# ESP_Batt_Board.net
KiCad netlist of a schematic drawn in Altium Designer
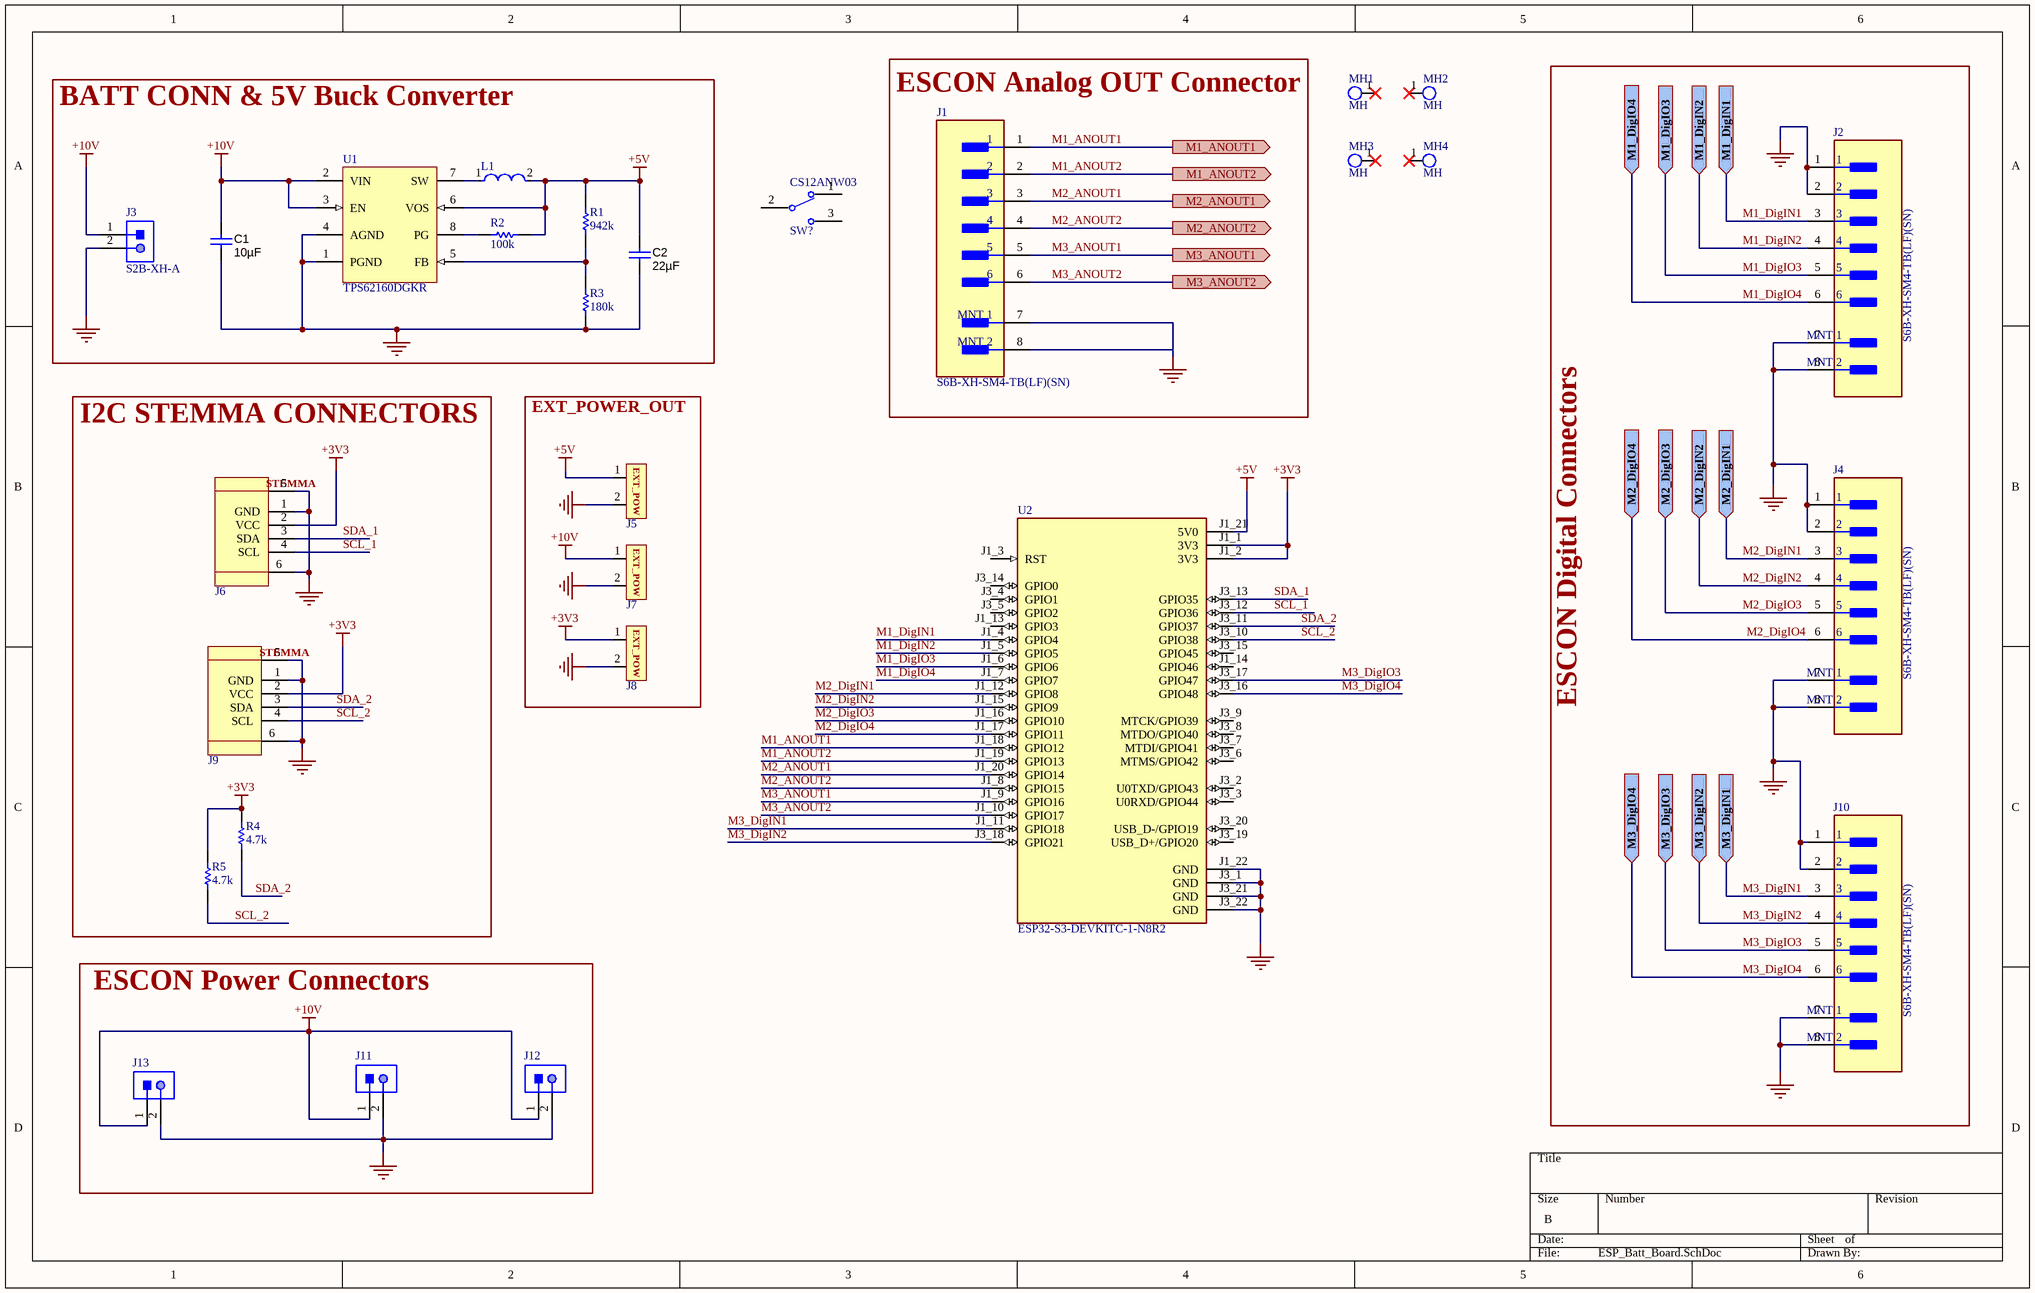
[diagram p0: ESP_Batt_Board.SchDoc]

(export (version "E")
  (design (tool "Eeschema 10.0.6"))
  (components
    (comp (ref "C1")
      (value "C2012X5R1E106K125AB")
      (footprint "CAP_0805")
      (description "CAP, CERM, 10uF, 25V, +/-10%, X5R, 0805")
      (fields
        (field (name "MANUFACTURER") "TDK")
        (field (name "VALUEDISPLAYED") "10µF")
        (field (name "PUBLISHER") "Texas Instruments")
      )
      (libsource (lib "Schematic") (part "C2012X5R1E106K125AB"))
    )
    (comp (ref "C2")
      (value "GRM21BR61E226ME44")
      (footprint "CAP_0805")
      (description "CAP, CERM, 22 µF, 25 V, +/- 20%, X5R, 0805")
      (fields (field (name "MANUFACTURER") "MuRata") (field (name "VALUEDISPLAYED") "22µF"))
      (libsource (lib "Schematic") (part "GRM21BR61E226ME44"))
    )
    (comp (ref "CS12ANW03")
      (value "SW?")
      (footprint "SPDT_SW")
      (libsource (lib "SchematicLib") (part "CS12ANW03"))
    )
    (comp (ref "J1")
      (value "S6B-XH-SM4-TB(LF)(SN)")
      (footprint "S6B-XH-SM4-TB")
      (description "CONN HEADER SMD R/A 6POS 2.5MM")
      (libsource (lib "") (part "S6B-XH-SM4-TB_1"))
    )
    (comp (ref "J2")
      (value "S6B-XH-SM4-TB(LF)(SN)")
      (footprint "S6B-XH-SM4-TB")
      (description "CONN HEADER SMD R/A 6POS 2.5MM")
      (libsource (lib "SchematicLib") (part "S6B-XH-SM4-TB"))
    )
    (comp (ref "J3")
      (value "S2B-XH-A")
      (footprint "JST-S2B-XH-A(LF)(SN)_V")
      (libsource (lib "SchematicLib") (part "S2B-XH-A"))
    )
    (comp (ref "J4")
      (value "S6B-XH-SM4-TB(LF)(SN)")
      (footprint "S6B-XH-SM4-TB")
      (description "CONN HEADER SMD R/A 6POS 2.5MM")
      (libsource (lib "SchematicLib") (part "S6B-XH-SM4-TB"))
    )
    (comp (ref "J5")
      (value "EXT_POWER_CONN")
      (footprint "EXTRA_POWR_CONN")
      (libsource (lib "SchematicLib") (part "EXT_POWER_CONN"))
    )
    (comp (ref "J6")
      (value "SM04B-SRSS-TB")
      (footprint "4PIN_STEMMA")
      (libsource (lib "SchematicLib") (part "SM04B-SRSS-TB"))
    )
    (comp (ref "J7")
      (value "EXT_POWER_CONN")
      (footprint "EXTRA_POWR_CONN")
      (libsource (lib "SchematicLib") (part "EXT_POWER_CONN"))
    )
    (comp (ref "J8")
      (value "EXT_POWER_CONN")
      (footprint "EXTRA_POWR_CONN")
      (libsource (lib "SchematicLib") (part "EXT_POWER_CONN"))
    )
    (comp (ref "J9")
      (value "SM04B-SRSS-TB")
      (footprint "4PIN_STEMMA")
      (libsource (lib "SchematicLib") (part "SM04B-SRSS-TB"))
    )
    (comp (ref "J10")
      (value "S6B-XH-SM4-TB(LF)(SN)")
      (footprint "S6B-XH-SM4-TB")
      (description "CONN HEADER SMD R/A 6POS 2.5MM")
      (libsource (lib "SchematicLib") (part "S6B-XH-SM4-TB"))
    )
    (comp (ref "J11")
      (value "S2B-XH-A")
      (footprint "JST-S2B-XH-A(LF)(SN)_V")
      (libsource (lib "") (part "S2B-XH-A_1"))
    )
    (comp (ref "J12")
      (value "S2B-XH-A")
      (footprint "JST-S2B-XH-A(LF)(SN)_V")
      (libsource (lib "") (part "S2B-XH-A_1"))
    )
    (comp (ref "J13")
      (value "S2B-XH-A")
      (footprint "JST-S2B-XH-A(LF)(SN)_V")
      (libsource (lib "") (part "S2B-XH-A_1"))
    )
    (comp (ref "L1")
      (value "IHLP1212BZEZ2R2M1Z")
      (footprint "IND_1212")
      (libsource (lib "SchematicLib") (part "IHLP1212BZEZ2R2M1Z"))
    )
    (comp (ref "MH1") (value "MH") (footprint "M3_MTH") (libsource (lib "SchematicLib") (part "M3_MTH")))
    (comp (ref "MH2") (value "MH") (footprint "M3_MTH") (libsource (lib "SchematicLib") (part "M3_MTH")))
    (comp (ref "MH3") (value "MH") (footprint "M3_MTH") (libsource (lib "SchematicLib") (part "M3_MTH")))
    (comp (ref "MH4") (value "MH") (footprint "M3_MTH") (libsource (lib "SchematicLib") (part "M3_MTH")))
    (comp (ref "R1") (value "942k") (footprint "RES_0603") (libsource (lib "SchematicLib") (part "RES_0603")))
    (comp (ref "R2") (value "100k") (footprint "RES_0603") (libsource (lib "SchematicLib") (part "RES_0603")))
    (comp (ref "R3") (value "180k") (footprint "RES_0603") (libsource (lib "SchematicLib") (part "RES_0603")))
    (comp (ref "R4") (value "4.7k") (footprint "RES_0603") (libsource (lib "SchematicLib") (part "RES_0603")))
    (comp (ref "R5") (value "4.7k") (footprint "RES_0603") (libsource (lib "SchematicLib") (part "RES_0603")))
    (comp (ref "U1")
      (value "TPS62160DGKR")
      (footprint "DGK0008A_M")
      (fields (field (name "MANUFACTURER") "Texas Instruments"))
      (libsource (lib "SchematicLib") (part "TPS62160DGKR"))
    )
    (comp (ref "U2")
      (value "ESP32-S3-DEVKITC-1-N8R2")
      (footprint "XCVR_ESP32-S3-DEVKITC-1-N8R2")
      (fields (field (name "MF") "Espressif Systems"))
      (libsource (lib "SchematicLib") (part "ESP32-S3-DEVKITC-1-N8R2"))
    )
  )
  (nets
    (net (code "1") (name "+3V3") (class "Default")
      (node (ref "J6") (pin "2") (pinfunction "VCC_2") (pintype "passive"))
      (node (ref "J8") (pin "1") (pinfunction "1_1") (pintype "passive"))
      (node (ref "J9") (pin "2") (pinfunction "VCC_2") (pintype "passive"))
      (node (ref "R4") (pin "2") (pinfunction "2_2") (pintype "passive"))
      (node (ref "R5") (pin "2") (pinfunction "2_2") (pintype "passive"))
      (node (ref "U2") (pin "J1_1") (pinfunction "3V3_J1_1") (pintype "power_in"))
      (node (ref "U2") (pin "J1_2") (pinfunction "3V3_J1_2") (pintype "power_in"))
    )
    (net (code "2") (name "+5V") (class "Default")
      (node (ref "C2") (pin "1") (pinfunction "1_1") (pintype "passive"))
      (node (ref "J5") (pin "1") (pinfunction "1_1") (pintype "passive"))
      (node (ref "L1") (pin "2") (pinfunction "2_2") (pintype "passive"))
      (node (ref "R1") (pin "2") (pinfunction "2_2") (pintype "passive"))
      (node (ref "R2") (pin "2") (pinfunction "2_2") (pintype "passive"))
      (node (ref "U1") (pin "6") (pinfunction "VOS_6") (pintype "input"))
      (node (ref "U2") (pin "J1_21") (pinfunction "5V0_J1_21") (pintype "power_in"))
    )
    (net (code "3") (name "+10V") (class "Default")
      (node (ref "C1") (pin "1") (pinfunction "1_1") (pintype "passive"))
      (node (ref "J11") (pin "1") (pinfunction "1_1") (pintype "passive"))
      (node (ref "J12") (pin "1") (pinfunction "1_1") (pintype "passive"))
      (node (ref "J13") (pin "1") (pinfunction "1_1") (pintype "passive"))
      (node (ref "J3") (pin "1") (pinfunction "1_1") (pintype "passive"))
      (node (ref "J7") (pin "1") (pinfunction "1_1") (pintype "passive"))
      (node (ref "U1") (pin "2") (pinfunction "VIN_2") (pintype "power_in"))
      (node (ref "U1") (pin "3") (pinfunction "EN_3") (pintype "input"))
    )
    (net (code "4") (name "/M1_ANOUT1") (class "Default")
      (node (ref "J1") (pin "1") (pinfunction "1_1") (pintype "passive"))
      (node (ref "U2") (pin "J1_18") (pinfunction "GPIO12_J1_18") (pintype "bidirectional"))
    )
    (net (code "5") (name "/M1_ANOUT2") (class "Default")
      (node (ref "J1") (pin "2") (pinfunction "2_2") (pintype "passive"))
      (node (ref "U2") (pin "J1_19") (pinfunction "GPIO13_J1_19") (pintype "bidirectional"))
    )
    (net (code "6") (name "/M1_DigIN1") (class "Default")
      (node (ref "J2") (pin "3") (pinfunction "3_3") (pintype "passive"))
      (node (ref "U2") (pin "J1_4") (pinfunction "GPIO4_J1_4") (pintype "bidirectional"))
    )
    (net (code "7") (name "/M1_DigIN2") (class "Default")
      (node (ref "J2") (pin "4") (pinfunction "4_4") (pintype "passive"))
      (node (ref "U2") (pin "J1_5") (pinfunction "GPIO5_J1_5") (pintype "bidirectional"))
    )
    (net (code "8") (name "/M1_DigIO3") (class "Default")
      (node (ref "J2") (pin "5") (pinfunction "5_5") (pintype "passive"))
      (node (ref "U2") (pin "J1_6") (pinfunction "GPIO6_J1_6") (pintype "bidirectional"))
    )
    (net (code "9") (name "/M1_DigIO4") (class "Default")
      (node (ref "J2") (pin "6") (pinfunction "6_6") (pintype "passive"))
      (node (ref "U2") (pin "J1_7") (pinfunction "GPIO7_J1_7") (pintype "bidirectional"))
    )
    (net (code "10") (name "/M2_ANOUT1") (class "Default")
      (node (ref "J1") (pin "3") (pinfunction "3_3") (pintype "passive"))
      (node (ref "U2") (pin "J1_20") (pinfunction "GPIO14_J1_20") (pintype "bidirectional"))
    )
    (net (code "11") (name "/M2_ANOUT2") (class "Default")
      (node (ref "J1") (pin "4") (pinfunction "4_4") (pintype "passive"))
      (node (ref "U2") (pin "J1_8") (pinfunction "GPIO15_J1_8") (pintype "bidirectional"))
    )
    (net (code "12") (name "/M2_DigIN1") (class "Default")
      (node (ref "J4") (pin "3") (pinfunction "3_3") (pintype "passive"))
      (node (ref "U2") (pin "J1_12") (pinfunction "GPIO8_J1_12") (pintype "bidirectional"))
    )
    (net (code "13") (name "/M2_DigIN2") (class "Default")
      (node (ref "J4") (pin "4") (pinfunction "4_4") (pintype "passive"))
      (node (ref "U2") (pin "J1_15") (pinfunction "GPIO9_J1_15") (pintype "bidirectional"))
    )
    (net (code "14") (name "/M2_DigIO3") (class "Default")
      (node (ref "J4") (pin "5") (pinfunction "5_5") (pintype "passive"))
      (node (ref "U2") (pin "J1_16") (pinfunction "GPIO10_J1_16") (pintype "bidirectional"))
    )
    (net (code "15") (name "/M2_DigIO4") (class "Default")
      (node (ref "J4") (pin "6") (pinfunction "6_6") (pintype "passive"))
      (node (ref "U2") (pin "J1_17") (pinfunction "GPIO11_J1_17") (pintype "bidirectional"))
    )
    (net (code "16") (name "/M3_ANOUT1") (class "Default")
      (node (ref "J1") (pin "5") (pinfunction "5_5") (pintype "passive"))
      (node (ref "U2") (pin "J1_9") (pinfunction "GPIO16_J1_9") (pintype "bidirectional"))
    )
    (net (code "17") (name "/M3_ANOUT2") (class "Default")
      (node (ref "J1") (pin "6") (pinfunction "6_6") (pintype "passive"))
      (node (ref "U2") (pin "J1_10") (pinfunction "GPIO17_J1_10") (pintype "bidirectional"))
    )
    (net (code "18") (name "/M3_DigIN1") (class "Default")
      (node (ref "J10") (pin "3") (pinfunction "3_3") (pintype "passive"))
      (node (ref "U2") (pin "J1_11") (pinfunction "GPIO18_J1_11") (pintype "bidirectional"))
    )
    (net (code "19") (name "/M3_DigIN2") (class "Default")
      (node (ref "J10") (pin "4") (pinfunction "4_4") (pintype "passive"))
      (node (ref "U2") (pin "J3_18") (pinfunction "GPIO21_J3_18") (pintype "bidirectional"))
    )
    (net (code "20") (name "/M3_DigIO3") (class "Default")
      (node (ref "J10") (pin "5") (pinfunction "5_5") (pintype "passive"))
      (node (ref "U2") (pin "J3_17") (pinfunction "GPIO47_J3_17") (pintype "bidirectional"))
    )
    (net (code "21") (name "/M3_DigIO4") (class "Default")
      (node (ref "J10") (pin "6") (pinfunction "6_6") (pintype "passive"))
      (node (ref "U2") (pin "J3_16") (pinfunction "GPIO48_J3_16") (pintype "bidirectional"))
    )
    (net (code "22") (name "/SCL_1") (class "Default")
      (node (ref "J6") (pin "4") (pinfunction "SCL_4") (pintype "passive"))
      (node (ref "U2") (pin "J3_12") (pinfunction "GPIO36_J3_12") (pintype "bidirectional"))
    )
    (net (code "23") (name "/SCL_2") (class "Default")
      (node (ref "J9") (pin "4") (pinfunction "SCL_4") (pintype "passive"))
      (node (ref "R5") (pin "1") (pinfunction "1_1") (pintype "passive"))
      (node (ref "U2") (pin "J3_10") (pinfunction "GPIO38_J3_10") (pintype "bidirectional"))
    )
    (net (code "24") (name "/SDA_1") (class "Default")
      (node (ref "J6") (pin "3") (pinfunction "SDA_3") (pintype "passive"))
      (node (ref "U2") (pin "J3_13") (pinfunction "GPIO35_J3_13") (pintype "bidirectional"))
    )
    (net (code "25") (name "/SDA_2") (class "Default")
      (node (ref "J9") (pin "3") (pinfunction "SDA_3") (pintype "passive"))
      (node (ref "R4") (pin "1") (pinfunction "1_1") (pintype "passive"))
      (node (ref "U2") (pin "J3_11") (pinfunction "GPIO37_J3_11") (pintype "bidirectional"))
    )
    (net (code "26") (name "GND") (class "Default")
      (node (ref "C1") (pin "2") (pinfunction "2_2") (pintype "passive"))
      (node (ref "C2") (pin "2") (pinfunction "2_2") (pintype "passive"))
      (node (ref "J1") (pin "7") (pinfunction "MNT_1_7") (pintype "passive"))
      (node (ref "J1") (pin "8") (pinfunction "MNT_2_8") (pintype "passive"))
      (node (ref "J10") (pin "1") (pinfunction "1_1") (pintype "passive"))
      (node (ref "J10") (pin "2") (pinfunction "2_2") (pintype "passive"))
      (node (ref "J10") (pin "7") (pinfunction "MNT_1_7") (pintype "passive"))
      (node (ref "J10") (pin "8") (pinfunction "MNT_2_8") (pintype "passive"))
      (node (ref "J11") (pin "2") (pinfunction "2_2") (pintype "passive"))
      (node (ref "J12") (pin "2") (pinfunction "2_2") (pintype "passive"))
      (node (ref "J13") (pin "2") (pinfunction "2_2") (pintype "passive"))
      (node (ref "J2") (pin "1") (pinfunction "1_1") (pintype "passive"))
      (node (ref "J2") (pin "2") (pinfunction "2_2") (pintype "passive"))
      (node (ref "J2") (pin "7") (pinfunction "MNT_1_7") (pintype "passive"))
      (node (ref "J2") (pin "8") (pinfunction "MNT_2_8") (pintype "passive"))
      (node (ref "J3") (pin "2") (pinfunction "2_2") (pintype "passive"))
      (node (ref "J4") (pin "1") (pinfunction "1_1") (pintype "passive"))
      (node (ref "J4") (pin "2") (pinfunction "2_2") (pintype "passive"))
      (node (ref "J4") (pin "7") (pinfunction "MNT_1_7") (pintype "passive"))
      (node (ref "J4") (pin "8") (pinfunction "MNT_2_8") (pintype "passive"))
      (node (ref "J5") (pin "2") (pinfunction "2_2") (pintype "passive"))
      (node (ref "J6") (pin "1") (pinfunction "GND_1") (pintype "passive"))
      (node (ref "J6") (pin "5") (pinfunction "MNT_5") (pintype "passive"))
      (node (ref "J7") (pin "2") (pinfunction "2_2") (pintype "passive"))
      (node (ref "J8") (pin "2") (pinfunction "2_2") (pintype "passive"))
      (node (ref "J9") (pin "1") (pinfunction "GND_1") (pintype "passive"))
      (node (ref "J9") (pin "5") (pinfunction "MNT_5") (pintype "passive"))
      (node (ref "R3") (pin "1") (pinfunction "1_1") (pintype "passive"))
      (node (ref "U1") (pin "1") (pinfunction "PGND_1") (pintype "power_in"))
      (node (ref "U1") (pin "4") (pinfunction "AGND_4") (pintype "power_in"))
      (node (ref "U2") (pin "J1_22") (pinfunction "GND_J1_22") (pintype "power_in"))
      (node (ref "U2") (pin "J3_1") (pinfunction "GND_J3_1") (pintype "power_in"))
      (node (ref "U2") (pin "J3_21") (pinfunction "GND_J3_21") (pintype "power_in"))
      (node (ref "U2") (pin "J3_22") (pinfunction "GND_J3_22") (pintype "power_in"))
    )
    (net (code "27") (name "Net-(U1-FB)") (class "Default")
      (node (ref "R1") (pin "1") (pinfunction "1_1") (pintype "passive"))
      (node (ref "R3") (pin "2") (pinfunction "2_2") (pintype "passive"))
      (node (ref "U1") (pin "5") (pinfunction "FB_5") (pintype "input"))
    )
    (net (code "28") (name "Net-(U1-PG)") (class "Default")
      (node (ref "R2") (pin "1") (pinfunction "1_1") (pintype "passive"))
      (node (ref "U1") (pin "8") (pinfunction "PG_8") (pintype "tri_state"))
    )
    (net (code "29") (name "Net-(U1-SW)") (class "Default")
      (node (ref "L1") (pin "1") (pinfunction "1_1") (pintype "passive"))
      (node (ref "U1") (pin "7") (pinfunction "SW_7") (pintype "power_in"))
    )
    (net (code "30") (name "unconnected-(CS12ANW03-2(COM)-Pad2)") (class "Default")
      (node (ref "CS12ANW03") (pin "2") (pinfunction "2(COM)_2") (pintype "passive"))
    )
    (net (code "31") (name "unconnected-(CS12ANW03-Pad1)") (class "Default")
      (node (ref "CS12ANW03") (pin "1") (pinfunction "1_1") (pintype "passive"))
    )
    (net (code "32") (name "unconnected-(CS12ANW03-Pad3)") (class "Default")
      (node (ref "CS12ANW03") (pin "3") (pinfunction "3_3") (pintype "passive"))
    )
    (net (code "33") (name "unconnected-(J6-MNT-Pad6)") (class "Default")
      (node (ref "J6") (pin "6") (pinfunction "MNT_6") (pintype "passive"))
    )
    (net (code "34") (name "unconnected-(J9-MNT-Pad6)") (class "Default")
      (node (ref "J9") (pin "6") (pinfunction "MNT_6") (pintype "passive"))
    )
    (net (code "35") (name "unconnected-(MH1-Pad1)") (class "Default")
      (node (ref "MH1") (pin "1") (pinfunction "1_1") (pintype "passive+no_connect"))
    )
    (net (code "36") (name "unconnected-(MH2-Pad1)") (class "Default")
      (node (ref "MH2") (pin "1") (pinfunction "1_1") (pintype "passive+no_connect"))
    )
    (net (code "37") (name "unconnected-(MH3-Pad1)") (class "Default")
      (node (ref "MH3") (pin "1") (pinfunction "1_1") (pintype "passive+no_connect"))
    )
    (net (code "38") (name "unconnected-(MH4-Pad1)") (class "Default")
      (node (ref "MH4") (pin "1") (pinfunction "1_1") (pintype "passive+no_connect"))
    )
    (net (code "39") (name "unconnected-(U2-GPIO0-PadJ3_14)") (class "Default")
      (node (ref "U2") (pin "J3_14") (pinfunction "GPIO0_J3_14") (pintype "bidirectional"))
    )
    (net (code "40") (name "unconnected-(U2-GPIO1-PadJ3_4)") (class "Default")
      (node (ref "U2") (pin "J3_4") (pinfunction "GPIO1_J3_4") (pintype "bidirectional"))
    )
    (net (code "41") (name "unconnected-(U2-GPIO2-PadJ3_5)") (class "Default")
      (node (ref "U2") (pin "J3_5") (pinfunction "GPIO2_J3_5") (pintype "bidirectional"))
    )
    (net (code "42") (name "unconnected-(U2-GPIO3-PadJ1_13)") (class "Default")
      (node (ref "U2") (pin "J1_13") (pinfunction "GPIO3_J1_13") (pintype "bidirectional"))
    )
    (net (code "43") (name "unconnected-(U2-GPIO45-PadJ3_15)") (class "Default")
      (node (ref "U2") (pin "J3_15") (pinfunction "GPIO45_J3_15") (pintype "bidirectional"))
    )
    (net (code "44") (name "unconnected-(U2-GPIO46-PadJ1_14)") (class "Default")
      (node (ref "U2") (pin "J1_14") (pinfunction "GPIO46_J1_14") (pintype "bidirectional"))
    )
    (net (code "45") (name "unconnected-(U2-MTCK{slash}GPIO39-PadJ3_9)") (class "Default")
      (node (ref "U2") (pin "J3_9") (pinfunction "MTCK/GPIO39_J3_9") (pintype "bidirectional"))
    )
    (net (code "46") (name "unconnected-(U2-MTDI{slash}GPIO41-PadJ3_7)") (class "Default")
      (node (ref "U2") (pin "J3_7") (pinfunction "MTDI/GPIO41_J3_7") (pintype "bidirectional"))
    )
    (net (code "47") (name "unconnected-(U2-MTDO{slash}GPIO40-PadJ3_8)") (class "Default")
      (node (ref "U2") (pin "J3_8") (pinfunction "MTDO/GPIO40_J3_8") (pintype "bidirectional"))
    )
    (net (code "48") (name "unconnected-(U2-MTMS{slash}GPIO42-PadJ3_6)") (class "Default")
      (node (ref "U2") (pin "J3_6") (pinfunction "MTMS/GPIO42_J3_6") (pintype "bidirectional"))
    )
    (net (code "49") (name "unconnected-(U2-RST-PadJ1_3)") (class "Default")
      (node (ref "U2") (pin "J1_3") (pinfunction "RST_J1_3") (pintype "input"))
    )
    (net (code "50") (name "unconnected-(U2-U0RXD{slash}GPIO44-PadJ3_3)") (class "Default")
      (node (ref "U2") (pin "J3_3") (pinfunction "U0RXD/GPIO44_J3_3") (pintype "bidirectional"))
    )
    (net (code "51") (name "unconnected-(U2-U0TXD{slash}GPIO43-PadJ3_2)") (class "Default")
      (node (ref "U2") (pin "J3_2") (pinfunction "U0TXD/GPIO43_J3_2") (pintype "bidirectional"))
    )
    (net (code "52") (name "unconnected-(U2-USB_D+{slash}GPIO20-PadJ3_19)") (class "Default")
      (node (ref "U2") (pin "J3_19") (pinfunction "USB_D+/GPIO20_J3_19") (pintype "bidirectional"))
    )
    (net (code "53") (name "unconnected-(U2-USB_D-{slash}GPIO19-PadJ3_20)") (class "Default")
      (node (ref "U2") (pin "J3_20") (pinfunction "USB_D-/GPIO19_J3_20") (pintype "bidirectional"))
    )
  )
)
